# Irdroid_USB.net
KiCad netlist of a schematic drawn in EAGLE
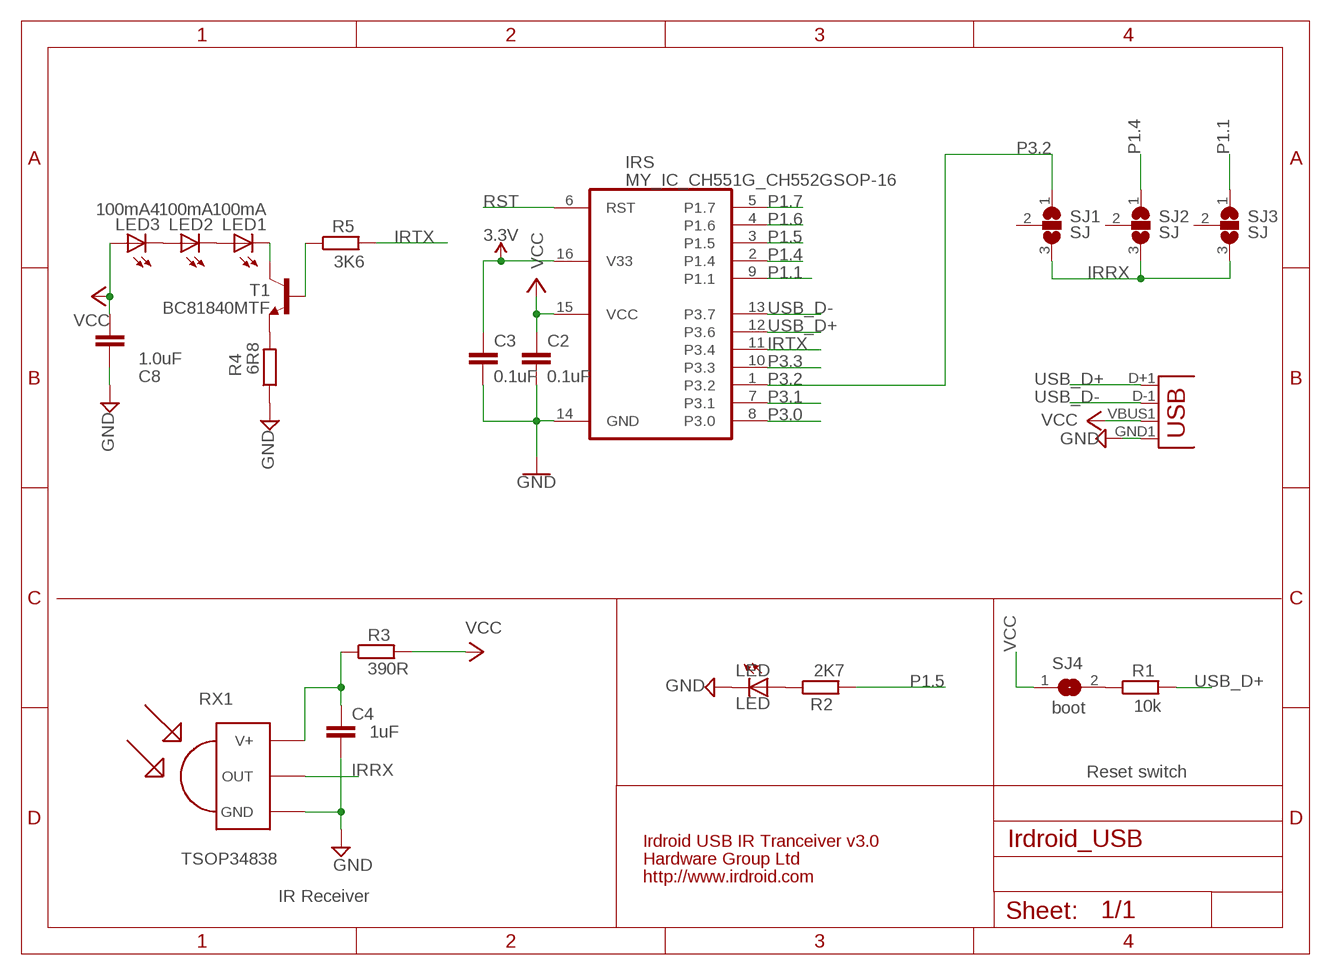
[diagram p0: schematic, sheet 1]

(export (version "E")
  (design (tool "Eeschema 10.0.6"))
  (components
    (comp (ref "C2")
      (value "0.1uF")
      (footprint "eagle-import:C0805K")
      (libsource (lib "eagle-import") (part "C-EUC0805K"))
    )
    (comp (ref "C3")
      (value "0.1uF")
      (footprint "eagle-import:C0805K")
      (libsource (lib "eagle-import") (part "C-EUC0805K"))
    )
    (comp (ref "C4")
      (value "1uF")
      (footprint "eagle-import:C603")
      (libsource (lib "eagle-import") (part "CAPC603"))
    )
    (comp (ref "C8")
      (value "1.0uF")
      (footprint "eagle-import:C603")
      (libsource (lib "eagle-import") (part "CAPC603"))
    )
    (comp (ref "IRS")
      (value "MY_IC_CH551G_CH552GSOP-16")
      (footprint "eagle-import:MY_IC_SO16")
      (libsource (lib "eagle-import") (part "MY_IC_CH551G_CH552GSOP-16"))
    )
    (comp (ref "JP2")
      (value "USBA-SMD-MALE")
      (footprint "eagle-import:USB-A-SMT-MALE")
      (libsource (lib "eagle-import") (part "USBA-SMD-MALE"))
    )
    (comp (ref "LED")
      (value "LED")
      (footprint "eagle-import:CHIP-LED0805")
      (libsource (lib "eagle-import") (part "LEDCHIP-LED0805"))
    )
    (comp (ref "LED1")
      (value "100mA")
      (footprint "eagle-import:LED3MM")
      (libsource (lib "eagle-import") (part "LED3MM"))
    )
    (comp (ref "LED2")
      (value "100mA")
      (footprint "eagle-import:LED3MM")
      (libsource (lib "eagle-import") (part "LED3MM"))
    )
    (comp (ref "LED3")
      (value "100mA4")
      (footprint "eagle-import:LED3MM")
      (libsource (lib "eagle-import") (part "LED3MM"))
    )
    (comp (ref "R1")
      (value "10k")
      (footprint "eagle-import:R603")
      (libsource (lib "eagle-import") (part "RESISTORR603"))
    )
    (comp (ref "R2")
      (value "2K7")
      (footprint "eagle-import:R603")
      (libsource (lib "eagle-import") (part "RESISTORR603"))
    )
    (comp (ref "R3")
      (value "390R")
      (footprint "eagle-import:R603")
      (libsource (lib "eagle-import") (part "RESISTORR603"))
    )
    (comp (ref "R4")
      (value "6R8")
      (footprint "eagle-import:M1206")
      (libsource (lib "eagle-import") (part "R-EU_M1206"))
    )
    (comp (ref "R5")
      (value "3K6")
      (footprint "eagle-import:R603")
      (libsource (lib "eagle-import") (part "RESISTORR603"))
    )
    (comp (ref "RX")
      (value "TSOP34838")
      (footprint "eagle-import:TSOP18XX")
      (libsource (lib "eagle-import") (part "TSOP4838"))
    )
    (comp (ref "SJ1")
      (value "SJ")
      (footprint "eagle-import:SJ_2")
      (libsource (lib "eagle-import") (part "SJ2W"))
    )
    (comp (ref "SJ2")
      (value "SJ")
      (footprint "eagle-import:SJ_2")
      (libsource (lib "eagle-import") (part "SJ2W"))
    )
    (comp (ref "SJ3")
      (value "SJ")
      (footprint "eagle-import:SJ_2")
      (libsource (lib "eagle-import") (part "SJ2W"))
    )
    (comp (ref "SJ4")
      (value "boot")
      (footprint "eagle-import:SJ")
      (libsource (lib "eagle-import") (part "SJ"))
    )
    (comp (ref "T1")
      (value "BC81840MTF")
      (footprint "eagle-import:SOT23-BEC")
      (libsource (lib "eagle-import") (part "NPNSOT23BEC"))
    )
  )
  (nets
    (net (code "1") (name "/IRRX") (class "Default")
      (node (ref "RX") (pin "OUT") (pinfunction "OUT_OUT") (pintype "bidirectional"))
      (node (ref "SJ1") (pin "3") (pinfunction "3_3") (pintype "passive"))
      (node (ref "SJ2") (pin "3") (pinfunction "3_3") (pintype "passive"))
      (node (ref "SJ3") (pin "3") (pinfunction "3_3") (pintype "passive"))
    )
    (net (code "2") (name "/IRTX") (class "Default")
      (node (ref "IRS") (pin "11") (pinfunction "P3.4_11") (pintype "bidirectional"))
      (node (ref "R5") (pin "2") (pinfunction "2_2") (pintype "passive"))
    )
    (net (code "3") (name "/P1.1") (class "Default")
      (node (ref "IRS") (pin "9") (pinfunction "P1.1_9") (pintype "bidirectional"))
      (node (ref "SJ3") (pin "1") (pinfunction "1_1") (pintype "passive"))
    )
    (net (code "4") (name "/P1.4") (class "Default")
      (node (ref "IRS") (pin "2") (pinfunction "P1.4_2") (pintype "bidirectional"))
      (node (ref "SJ2") (pin "1") (pinfunction "1_1") (pintype "passive"))
    )
    (net (code "5") (name "/P1.5") (class "Default")
      (node (ref "IRS") (pin "3") (pinfunction "P1.5_3") (pintype "bidirectional"))
      (node (ref "R2") (pin "2") (pinfunction "2_2") (pintype "passive"))
    )
    (net (code "6") (name "/P1.6") (class "Default")
      (node (ref "IRS") (pin "4") (pinfunction "P1.6_4") (pintype "bidirectional"))
    )
    (net (code "7") (name "/P1.7") (class "Default")
      (node (ref "IRS") (pin "5") (pinfunction "P1.7_5") (pintype "bidirectional"))
    )
    (net (code "8") (name "/P3.0") (class "Default")
      (node (ref "IRS") (pin "8") (pinfunction "P3.0_8") (pintype "bidirectional"))
    )
    (net (code "9") (name "/P3.1") (class "Default")
      (node (ref "IRS") (pin "7") (pinfunction "P3.1_7") (pintype "bidirectional"))
    )
    (net (code "10") (name "/P3.2") (class "Default")
      (node (ref "IRS") (pin "1") (pinfunction "P3.2_1") (pintype "bidirectional"))
      (node (ref "SJ1") (pin "1") (pinfunction "1_1") (pintype "passive"))
    )
    (net (code "11") (name "/P3.3") (class "Default")
      (node (ref "IRS") (pin "10") (pinfunction "P3.3_10") (pintype "bidirectional"))
    )
    (net (code "12") (name "/RST") (class "Default")
      (node (ref "IRS") (pin "6") (pinfunction "RST_6") (pintype "input"))
    )
    (net (code "13") (name "/USB_D+") (class "Default")
      (node (ref "IRS") (pin "12") (pinfunction "P3.6_12") (pintype "bidirectional"))
      (node (ref "JP2") (pin "D+1") (pinfunction "D+_D+1") (pintype "bidirectional"))
      (node (ref "R1") (pin "2") (pinfunction "2_2") (pintype "passive"))
    )
    (net (code "14") (name "/USB_D-") (class "Default")
      (node (ref "IRS") (pin "13") (pinfunction "P3.7_13") (pintype "bidirectional"))
      (node (ref "JP2") (pin "D-1") (pinfunction "D-_D-1") (pintype "bidirectional"))
    )
    (net (code "15") (name "3.3V") (class "Default")
      (node (ref "C3") (pin "1") (pinfunction "1_1") (pintype "passive"))
      (node (ref "IRS") (pin "16") (pinfunction "V33_16") (pintype "power_in"))
    )
    (net (code "16") (name "GND") (class "Default")
      (node (ref "C2") (pin "2") (pinfunction "2_2") (pintype "passive"))
      (node (ref "C3") (pin "2") (pinfunction "2_2") (pintype "passive"))
      (node (ref "C4") (pin "2") (pinfunction "2_2") (pintype "passive"))
      (node (ref "C8") (pin "2") (pinfunction "2_2") (pintype "passive"))
      (node (ref "IRS") (pin "14") (pinfunction "GND_14") (pintype "power_in"))
      (node (ref "JP2") (pin "GND1") (pinfunction "GND_GND1") (pintype "bidirectional"))
      (node (ref "LED") (pin "C") (pinfunction "C_C") (pintype "passive"))
      (node (ref "R4") (pin "1") (pinfunction "1_1") (pintype "passive"))
      (node (ref "RX") (pin "GND") (pinfunction "GND_GND") (pintype "bidirectional"))
    )
    (net (code "17") (name "Net-(LED-PadA)") (class "Default")
      (node (ref "LED") (pin "A") (pinfunction "A_A") (pintype "passive"))
      (node (ref "R2") (pin "1") (pinfunction "1_1") (pintype "passive"))
    )
    (net (code "18") (name "Net-(LED1-C)") (class "Default")
      (node (ref "LED1") (pin "K") (pinfunction "C_K") (pintype "passive"))
      (node (ref "T1") (pin "C") (pinfunction "C_C") (pintype "passive"))
    )
    (net (code "19") (name "Net-(LED2-C)") (class "Default")
      (node (ref "LED1") (pin "A") (pinfunction "A_A") (pintype "passive"))
      (node (ref "LED2") (pin "K") (pinfunction "C_K") (pintype "passive"))
    )
    (net (code "20") (name "Net-(LED3-C)") (class "Default")
      (node (ref "LED2") (pin "A") (pinfunction "A_A") (pintype "passive"))
      (node (ref "LED3") (pin "K") (pinfunction "C_K") (pintype "passive"))
    )
    (net (code "21") (name "Net-(R1-Pad1)") (class "Default")
      (node (ref "R1") (pin "1") (pinfunction "1_1") (pintype "passive"))
      (node (ref "SJ4") (pin "2") (pinfunction "2_2") (pintype "passive"))
    )
    (net (code "22") (name "Net-(R4-Pad2)") (class "Default")
      (node (ref "R4") (pin "2") (pinfunction "2_2") (pintype "passive"))
      (node (ref "T1") (pin "E") (pinfunction "E_E") (pintype "passive"))
    )
    (net (code "23") (name "Net-(R5-Pad1)") (class "Default")
      (node (ref "R5") (pin "1") (pinfunction "1_1") (pintype "passive"))
      (node (ref "T1") (pin "B") (pinfunction "B_B") (pintype "passive"))
    )
    (net (code "24") (name "Net-(RX-V+)") (class "Default")
      (node (ref "C4") (pin "1") (pinfunction "1_1") (pintype "passive"))
      (node (ref "R3") (pin "1") (pinfunction "1_1") (pintype "passive"))
      (node (ref "RX") (pin "VCC") (pinfunction "V+_VCC") (pintype "bidirectional"))
    )
    (net (code "25") (name "VCC") (class "Default")
      (node (ref "C2") (pin "1") (pinfunction "1_1") (pintype "passive"))
      (node (ref "C8") (pin "1") (pinfunction "1_1") (pintype "passive"))
      (node (ref "IRS") (pin "15") (pinfunction "VCC_15") (pintype "power_in"))
      (node (ref "JP2") (pin "VBUS1") (pinfunction "VBUS_VBUS1") (pintype "bidirectional"))
      (node (ref "LED3") (pin "A") (pinfunction "A_A") (pintype "passive"))
      (node (ref "R3") (pin "2") (pinfunction "2_2") (pintype "passive"))
      (node (ref "SJ4") (pin "1") (pinfunction "1_1") (pintype "passive"))
    )
    (net (code "26") (name "unconnected-(SJ1-Pad2)") (class "Default")
      (node (ref "SJ1") (pin "2") (pinfunction "2_2") (pintype "passive"))
    )
    (net (code "27") (name "unconnected-(SJ2-Pad2)") (class "Default")
      (node (ref "SJ2") (pin "2") (pinfunction "2_2") (pintype "passive"))
    )
    (net (code "28") (name "unconnected-(SJ3-Pad2)") (class "Default")
      (node (ref "SJ3") (pin "2") (pinfunction "2_2") (pintype "passive"))
    )
  )
)
